# water_ver3_0_0.net
KiCad netlist of a schematic drawn in EAGLE
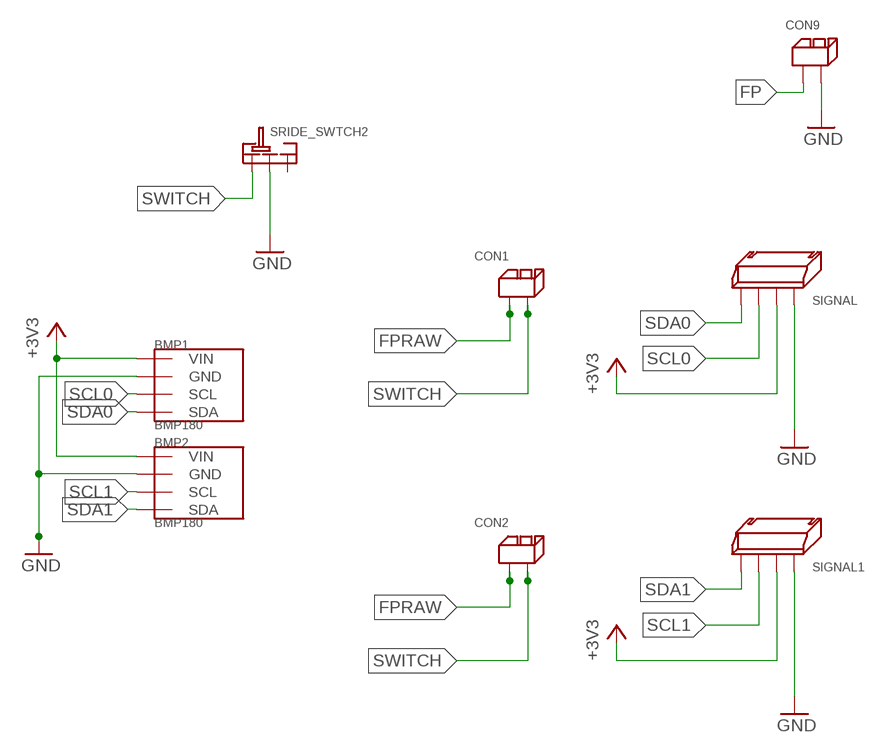
[diagram p0: schematic, sheet 1]

(export (version "E")
  (design (tool "Eeschema 10.0.6"))
  (components
    (comp (ref "BMP1")
      (value "BMP180")
      (footprint "eagle-import:GY-68")
      (libsource (lib "eagle-import") (part "BMP180"))
    )
    (comp (ref "BMP2")
      (value "BMP180")
      (footprint "eagle-import:GY-68")
      (libsource (lib "eagle-import") (part "BMP180"))
    )
    (comp (ref "CON1")
      (value "2PIN")
      (footprint "eagle-import:2PIN")
      (libsource (lib "eagle-import") (part "2PIN"))
    )
    (comp (ref "CON2")
      (value "2PIN")
      (footprint "eagle-import:2PIN")
      (libsource (lib "eagle-import") (part "2PIN"))
    )
    (comp (ref "CON9")
      (value "2PIN")
      (footprint "eagle-import:2PIN")
      (libsource (lib "eagle-import") (part "2PIN"))
    )
    (comp (ref "SIGNAL")
      (value "4PIN_SIDE")
      (footprint "eagle-import:4PIN_SIDE")
      (libsource (lib "eagle-import") (part "4PIN_SIDE"))
    )
    (comp (ref "SIGNAL1")
      (value "4PIN_SIDE")
      (footprint "eagle-import:4PIN_SIDE")
      (libsource (lib "eagle-import") (part "4PIN_SIDE"))
    )
    (comp (ref "SRIDE_SWTCH2")
      (value "SRIDE_SWITCH")
      (footprint "eagle-import:SRIDE_SWITCH")
      (libsource (lib "eagle-import") (part "SRIDE_SWITCH"))
    )
  )
  (nets
    (net (code "1") (name "+3V3") (class "Default")
      (node (ref "BMP1") (pin "P1") (pinfunction "VIN_P1") (pintype "bidirectional"))
      (node (ref "BMP2") (pin "P1") (pinfunction "VIN_P1") (pintype "bidirectional"))
      (node (ref "SIGNAL") (pin "P$3") (pinfunction "P$3_P$3") (pintype "bidirectional"))
      (node (ref "SIGNAL1") (pin "P$3") (pinfunction "P$3_P$3") (pintype "bidirectional"))
    )
    (net (code "2") (name "FP") (class "Default")
      (node (ref "CON9") (pin "P$1") (pinfunction "P$1_P$1") (pintype "bidirectional"))
    )
    (net (code "3") (name "FPRAW") (class "Default")
      (node (ref "CON1") (pin "P$1") (pinfunction "P$1_P$1") (pintype "bidirectional"))
      (node (ref "CON2") (pin "P$1") (pinfunction "P$1_P$1") (pintype "bidirectional"))
    )
    (net (code "4") (name "GND") (class "Default")
      (node (ref "BMP1") (pin "P2") (pinfunction "GND_P2") (pintype "bidirectional"))
      (node (ref "BMP2") (pin "P2") (pinfunction "GND_P2") (pintype "bidirectional"))
      (node (ref "CON9") (pin "P$2") (pinfunction "P$2_P$2") (pintype "bidirectional"))
      (node (ref "SIGNAL") (pin "P$4") (pinfunction "P$4_P$4") (pintype "bidirectional"))
      (node (ref "SIGNAL1") (pin "P$4") (pinfunction "P$4_P$4") (pintype "bidirectional"))
      (node (ref "SRIDE_SWTCH2") (pin "LR") (pinfunction "LR_LR") (pintype "bidirectional"))
    )
    (net (code "5") (name "SCL0") (class "Default")
      (node (ref "BMP1") (pin "P3") (pinfunction "SCL_P3") (pintype "bidirectional"))
      (node (ref "SIGNAL") (pin "P$1") (pinfunction "P$1_P$1") (pintype "bidirectional"))
    )
    (net (code "6") (name "SCL1") (class "Default")
      (node (ref "BMP2") (pin "P3") (pinfunction "SCL_P3") (pintype "bidirectional"))
      (node (ref "SIGNAL1") (pin "P$1") (pinfunction "P$1_P$1") (pintype "bidirectional"))
    )
    (net (code "7") (name "SDA0") (class "Default")
      (node (ref "BMP1") (pin "P4") (pinfunction "SDA_P4") (pintype "bidirectional"))
      (node (ref "SIGNAL") (pin "P$2") (pinfunction "P$2_P$2") (pintype "bidirectional"))
    )
    (net (code "8") (name "SDA1") (class "Default")
      (node (ref "BMP2") (pin "P4") (pinfunction "SDA_P4") (pintype "bidirectional"))
      (node (ref "SIGNAL1") (pin "P$2") (pinfunction "P$2_P$2") (pintype "bidirectional"))
    )
    (net (code "9") (name "SWITCH") (class "Default")
      (node (ref "CON1") (pin "P$2") (pinfunction "P$2_P$2") (pintype "bidirectional"))
      (node (ref "CON2") (pin "P$2") (pinfunction "P$2_P$2") (pintype "bidirectional"))
      (node (ref "SRIDE_SWTCH2") (pin "L") (pinfunction "L_L") (pintype "bidirectional"))
    )
    (net (code "10") (name "unconnected-(SRIDE_SWTCH2-PadR)") (class "Default")
      (node (ref "SRIDE_SWTCH2") (pin "R") (pinfunction "R_R") (pintype "bidirectional"))
    )
  )
)
